# shutoff.net
KiCad netlist of a schematic drawn in EAGLE
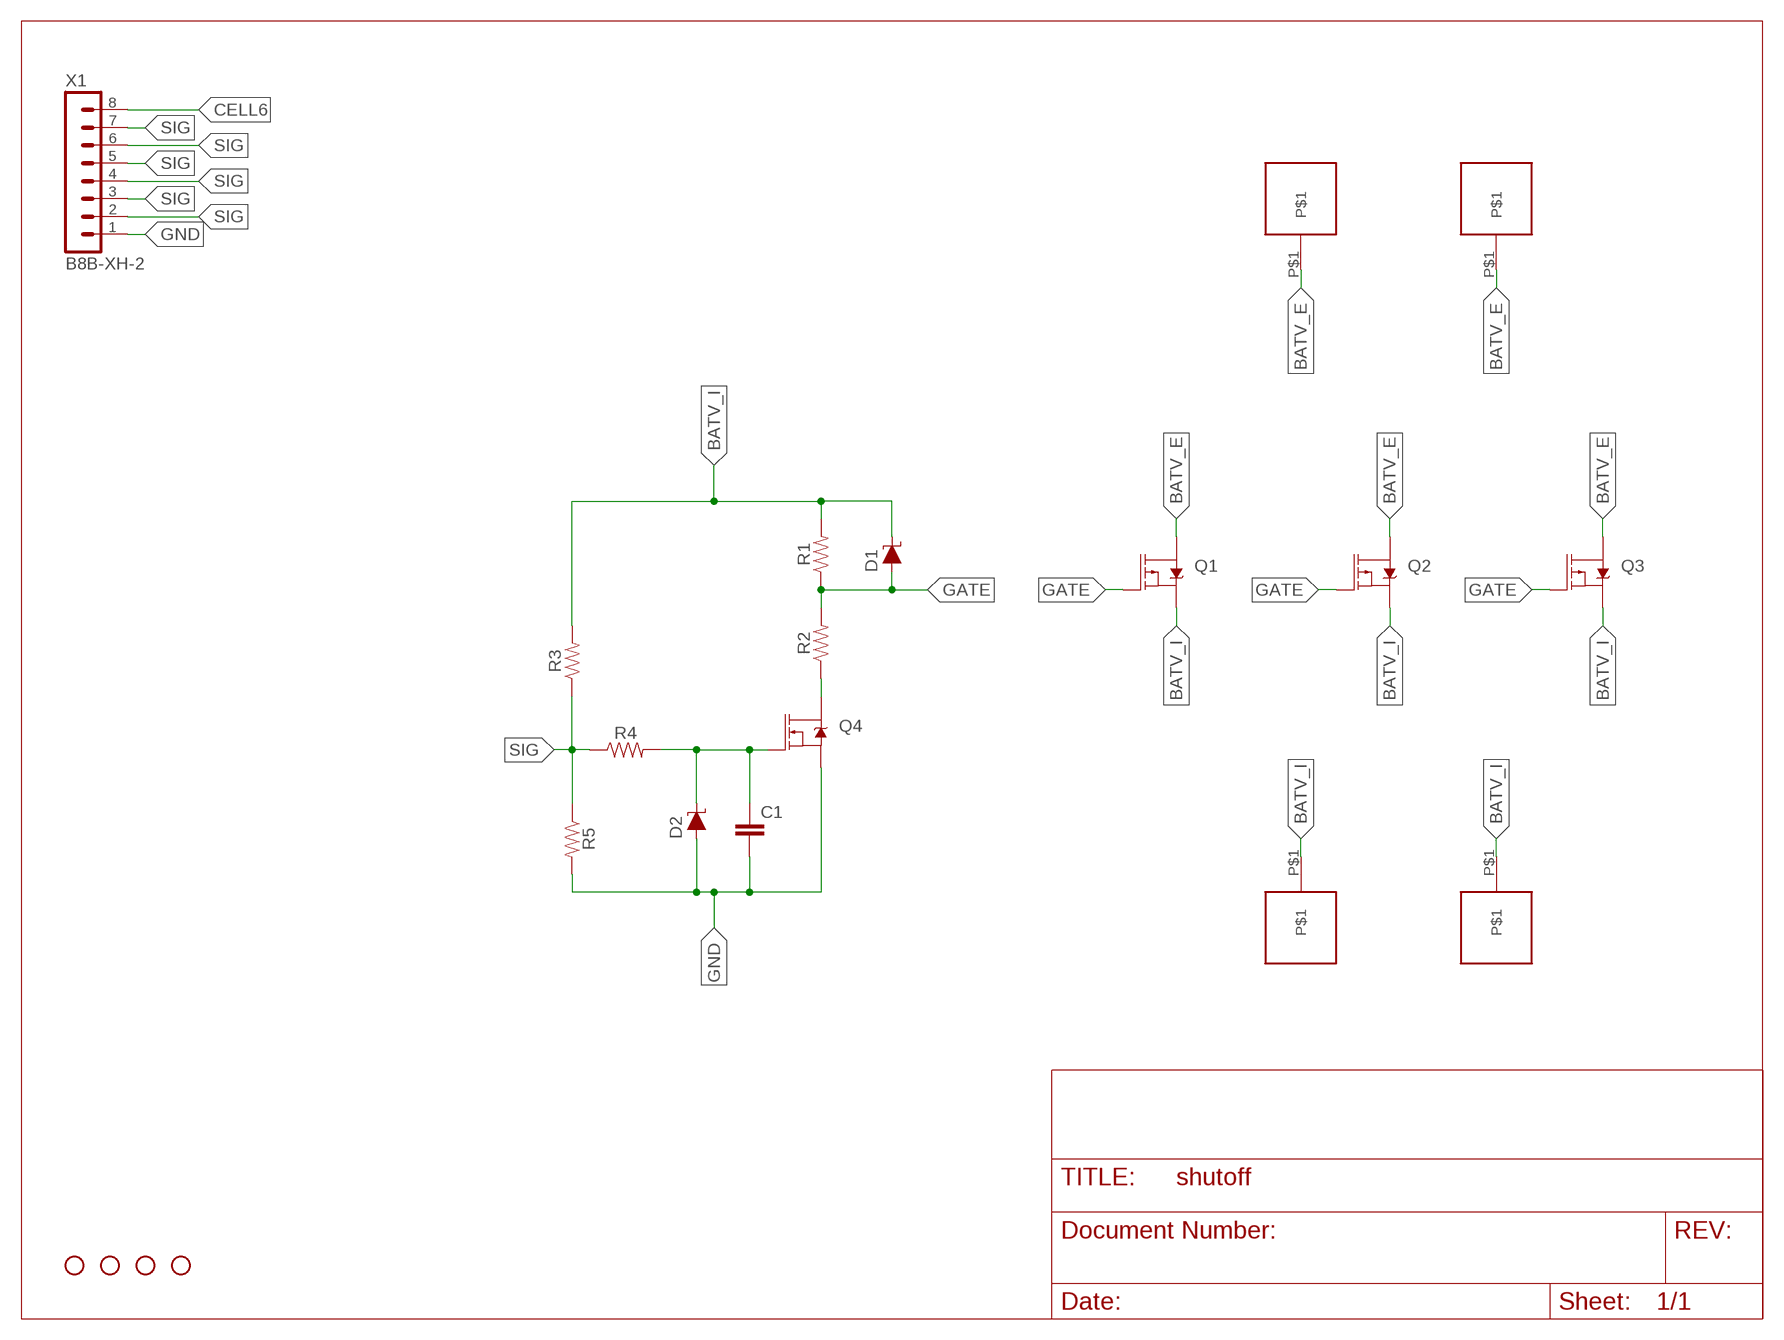
[diagram p0: schematic, sheet 1]

(export (version "E")
  (design (tool "Eeschema 10.0.6"))
  (components
    (comp (ref "C1")
      (value "CAPACITOR_0805")
      (footprint "eagle-import:0805")
      (libsource (lib "eagle-import") (part "CAPACITOR_0805"))
    )
    (comp (ref "D1")
      (value "DIODE_TVS_DO-214AA")
      (footprint "eagle-import:DO214AA")
      (libsource (lib "eagle-import") (part "DIODE_TVS_DO-214AA"))
    )
    (comp (ref "D2")
      (value "DIODE_TVS_DO-214AA")
      (footprint "eagle-import:DO214AA")
      (libsource (lib "eagle-import") (part "DIODE_TVS_DO-214AA"))
    )
    (comp (ref "H1")
      (value "STAND-OFF")
      (footprint "eagle-import:STAND-OFF")
      (libsource (lib "eagle-import") (part "STAND-OFF"))
    )
    (comp (ref "H2")
      (value "STAND-OFF")
      (footprint "eagle-import:STAND-OFF")
      (libsource (lib "eagle-import") (part "STAND-OFF"))
    )
    (comp (ref "H3")
      (value "STAND-OFF")
      (footprint "eagle-import:STAND-OFF")
      (libsource (lib "eagle-import") (part "STAND-OFF"))
    )
    (comp (ref "H4")
      (value "STAND-OFF")
      (footprint "eagle-import:STAND-OFF")
      (libsource (lib "eagle-import") (part "STAND-OFF"))
    )
    (comp (ref "Q1")
      (value "MOSFET_PMOS_TO-263")
      (footprint "eagle-import:TO-263_D2PAK")
      (libsource (lib "eagle-import") (part "MOSFET_PMOS_TO-263"))
    )
    (comp (ref "Q2")
      (value "MOSFET_PMOS_TO-263")
      (footprint "eagle-import:TO-263_D2PAK")
      (libsource (lib "eagle-import") (part "MOSFET_PMOS_TO-263"))
    )
    (comp (ref "Q3")
      (value "MOSFET_PMOS_TO-263")
      (footprint "eagle-import:TO-263_D2PAK")
      (libsource (lib "eagle-import") (part "MOSFET_PMOS_TO-263"))
    )
    (comp (ref "Q4")
      (value "MOSFET_NMOS_TO-263")
      (footprint "eagle-import:TO-263_D2PAK")
      (libsource (lib "eagle-import") (part "MOSFET_NMOS_TO-263"))
    )
    (comp (ref "R1")
      (value "RESISTOR_0805")
      (footprint "eagle-import:0805")
      (libsource (lib "eagle-import") (part "RESISTOR_0805"))
    )
    (comp (ref "R2")
      (value "RESISTOR_0805")
      (footprint "eagle-import:0805")
      (libsource (lib "eagle-import") (part "RESISTOR_0805"))
    )
    (comp (ref "R3")
      (value "RESISTOR_0805")
      (footprint "eagle-import:0805")
      (libsource (lib "eagle-import") (part "RESISTOR_0805"))
    )
    (comp (ref "R4")
      (value "RESISTOR_0805")
      (footprint "eagle-import:0805")
      (libsource (lib "eagle-import") (part "RESISTOR_0805"))
    )
    (comp (ref "R5")
      (value "RESISTOR_0805")
      (footprint "eagle-import:0805")
      (libsource (lib "eagle-import") (part "RESISTOR_0805"))
    )
    (comp (ref "W1")
      (value "16G")
      (footprint "eagle-import:16G")
      (libsource (lib "eagle-import") (part "16G"))
    )
    (comp (ref "W2")
      (value "16G")
      (footprint "eagle-import:16G")
      (libsource (lib "eagle-import") (part "16G"))
    )
    (comp (ref "W3")
      (value "16G")
      (footprint "eagle-import:16G")
      (libsource (lib "eagle-import") (part "16G"))
    )
    (comp (ref "W4")
      (value "16G")
      (footprint "eagle-import:16G")
      (libsource (lib "eagle-import") (part "16G"))
    )
    (comp (ref "X1")
      (value "B8B-XH-2")
      (footprint "eagle-import:B8B-XH-A")
      (libsource (lib "eagle-import") (part "B8B-XH-2"))
    )
  )
  (nets
    (net (code "1") (name "BATV_E") (class "Default")
      (node (ref "Q1") (pin "2") (pinfunction "D_2") (pintype "bidirectional"))
      (node (ref "Q2") (pin "2") (pinfunction "D_2") (pintype "bidirectional"))
      (node (ref "Q3") (pin "2") (pinfunction "D_2") (pintype "bidirectional"))
      (node (ref "W1") (pin "P$1") (pinfunction "P$1_P$1") (pintype "bidirectional"))
      (node (ref "W2") (pin "P$1") (pinfunction "P$1_P$1") (pintype "bidirectional"))
    )
    (net (code "2") (name "BATV_I") (class "Default")
      (node (ref "D1") (pin "C") (pinfunction "C_C") (pintype "passive"))
      (node (ref "Q1") (pin "3") (pinfunction "S_3") (pintype "bidirectional"))
      (node (ref "Q2") (pin "3") (pinfunction "S_3") (pintype "bidirectional"))
      (node (ref "Q3") (pin "3") (pinfunction "S_3") (pintype "bidirectional"))
      (node (ref "R1") (pin "2") (pinfunction "2_2") (pintype "passive"))
      (node (ref "R3") (pin "2") (pinfunction "2_2") (pintype "passive"))
      (node (ref "W3") (pin "P$1") (pinfunction "P$1_P$1") (pintype "bidirectional"))
      (node (ref "W4") (pin "P$1") (pinfunction "P$1_P$1") (pintype "bidirectional"))
    )
    (net (code "3") (name "CELL6") (class "Default")
      (node (ref "X1") (pin "8") (pinfunction "8_8") (pintype "passive"))
    )
    (net (code "4") (name "GATE") (class "Default")
      (node (ref "D1") (pin "A") (pinfunction "A_A") (pintype "passive"))
      (node (ref "Q1") (pin "1") (pinfunction "G_1") (pintype "bidirectional"))
      (node (ref "Q2") (pin "1") (pinfunction "G_1") (pintype "bidirectional"))
      (node (ref "Q3") (pin "1") (pinfunction "G_1") (pintype "bidirectional"))
      (node (ref "R1") (pin "1") (pinfunction "1_1") (pintype "passive"))
      (node (ref "R2") (pin "2") (pinfunction "2_2") (pintype "passive"))
    )
    (net (code "5") (name "GND") (class "Default")
      (node (ref "C1") (pin "2") (pinfunction "2_2") (pintype "passive"))
      (node (ref "D2") (pin "A") (pinfunction "A_A") (pintype "passive"))
      (node (ref "Q4") (pin "3") (pinfunction "S_3") (pintype "bidirectional"))
      (node (ref "R5") (pin "2") (pinfunction "2_2") (pintype "passive"))
      (node (ref "X1") (pin "1") (pinfunction "1_1") (pintype "passive"))
    )
    (net (code "6") (name "Net-(Q4-D)") (class "Default")
      (node (ref "Q4") (pin "2") (pinfunction "D_2") (pintype "bidirectional"))
      (node (ref "R2") (pin "1") (pinfunction "1_1") (pintype "passive"))
    )
    (net (code "7") (name "Net-(Q4-G)") (class "Default")
      (node (ref "C1") (pin "1") (pinfunction "1_1") (pintype "passive"))
      (node (ref "D2") (pin "C") (pinfunction "C_C") (pintype "passive"))
      (node (ref "Q4") (pin "1") (pinfunction "G_1") (pintype "bidirectional"))
      (node (ref "R4") (pin "2") (pinfunction "2_2") (pintype "passive"))
    )
    (net (code "8") (name "SIG") (class "Default")
      (node (ref "R3") (pin "1") (pinfunction "1_1") (pintype "passive"))
      (node (ref "R4") (pin "1") (pinfunction "1_1") (pintype "passive"))
      (node (ref "R5") (pin "1") (pinfunction "1_1") (pintype "passive"))
      (node (ref "X1") (pin "2") (pinfunction "2_2") (pintype "passive"))
      (node (ref "X1") (pin "3") (pinfunction "3_3") (pintype "passive"))
      (node (ref "X1") (pin "4") (pinfunction "4_4") (pintype "passive"))
      (node (ref "X1") (pin "5") (pinfunction "5_5") (pintype "passive"))
      (node (ref "X1") (pin "6") (pinfunction "6_6") (pintype "passive"))
      (node (ref "X1") (pin "7") (pinfunction "7_7") (pintype "passive"))
    )
  )
)
